# LightBoard.net
KiCad netlist of a schematic drawn in EAGLE
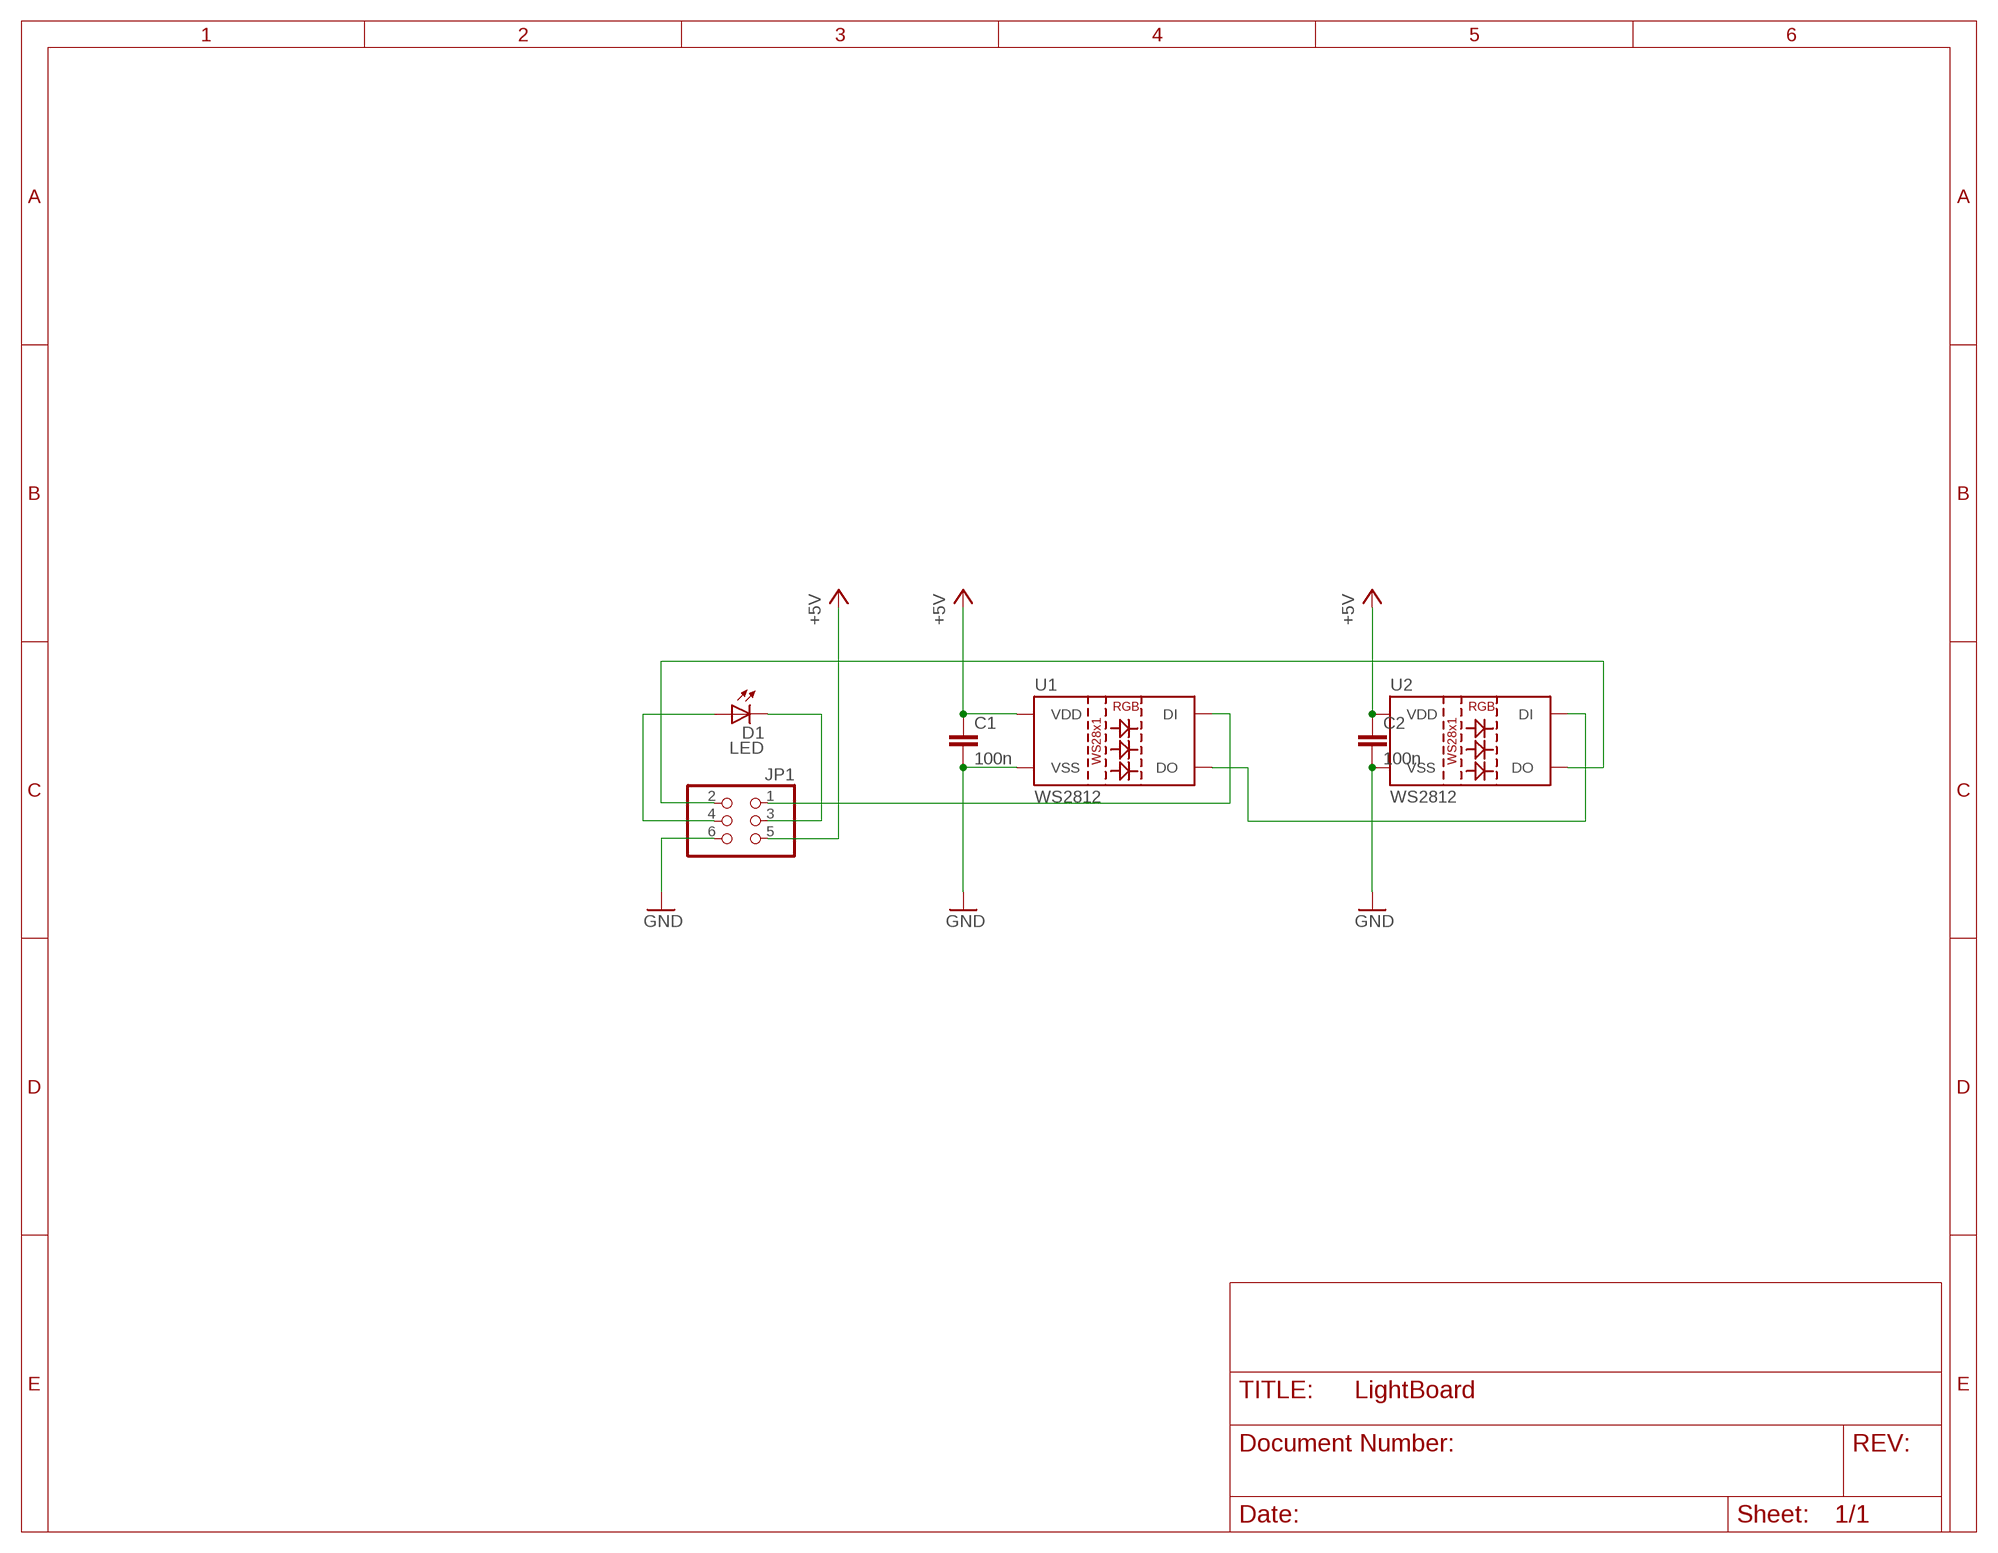
[diagram p0: schematic, sheet 1]

(export (version "E")
  (design (tool "Eeschema 10.0.6"))
  (components
    (comp (ref "C1")
      (value "100n")
      (footprint "eagle-import:C0603")
      (libsource (lib "eagle-import") (part "C-EUC0603"))
    )
    (comp (ref "C2")
      (value "100n")
      (footprint "eagle-import:C0603")
      (libsource (lib "eagle-import") (part "C-EUC0603"))
    )
    (comp (ref "D1")
      (value "LED")
      (footprint "eagle-import:LM561C")
      (libsource (lib "eagle-import") (part "LED"))
    )
    (comp (ref "JP1")
      (value "PINHD-2X3_2.54-SMD-90°")
      (footprint "eagle-import:2X03SMD_90")
      (libsource (lib "eagle-import") (part "PINHD-2X3_2.54-SMD-90°"))
    )
    (comp (ref "U1")
      (value "WS2812")
      (footprint "eagle-import:LED-TRICOLOR-5050-IC")
      (libsource (lib "eagle-import") (part "WS2812{dblquote}"))
    )
    (comp (ref "U2")
      (value "WS2812")
      (footprint "eagle-import:LED-TRICOLOR-5050-IC")
      (libsource (lib "eagle-import") (part "WS2812{dblquote}"))
    )
  )
  (nets
    (net (code "1") (name "+5V") (class "Default")
      (node (ref "C1") (pin "1") (pinfunction "1_1") (pintype "passive"))
      (node (ref "C2") (pin "1") (pinfunction "1_1") (pintype "passive"))
      (node (ref "JP1") (pin "5") (pinfunction "5_5") (pintype "passive"))
      (node (ref "U1") (pin "3") (pinfunction "VDD_3") (pintype "bidirectional"))
      (node (ref "U1") (pin "5") (pinfunction "VDD_5") (pintype "bidirectional"))
      (node (ref "U2") (pin "3") (pinfunction "VDD_3") (pintype "bidirectional"))
      (node (ref "U2") (pin "5") (pinfunction "VDD_5") (pintype "bidirectional"))
    )
    (net (code "2") (name "GND") (class "Default")
      (node (ref "C1") (pin "2") (pinfunction "2_2") (pintype "passive"))
      (node (ref "C2") (pin "2") (pinfunction "2_2") (pintype "passive"))
      (node (ref "JP1") (pin "6") (pinfunction "6_6") (pintype "passive"))
      (node (ref "U1") (pin "6") (pinfunction "VSS_6") (pintype "bidirectional"))
      (node (ref "U2") (pin "6") (pinfunction "VSS_6") (pintype "bidirectional"))
    )
    (net (code "3") (name "Net-(D1-A-PadA1)") (class "Default")
      (node (ref "D1") (pin "A1") (pinfunction "A_A1") (pintype "passive"))
      (node (ref "D1") (pin "A2") (pinfunction "A_A2") (pintype "passive"))
      (node (ref "D1") (pin "A3") (pinfunction "A_A3") (pintype "passive"))
      (node (ref "JP1") (pin "4") (pinfunction "4_4") (pintype "passive"))
    )
    (net (code "4") (name "Net-(D1-C-PadC1)") (class "Default")
      (node (ref "D1") (pin "C1") (pinfunction "C_C1") (pintype "passive"))
      (node (ref "D1") (pin "C2") (pinfunction "C_C2") (pintype "passive"))
      (node (ref "D1") (pin "C3") (pinfunction "C_C3") (pintype "passive"))
      (node (ref "JP1") (pin "3") (pinfunction "3_3") (pintype "passive"))
    )
    (net (code "5") (name "Net-(U1-DI)") (class "Default")
      (node (ref "JP1") (pin "1") (pinfunction "1_1") (pintype "passive"))
      (node (ref "U1") (pin "2") (pinfunction "DI_2") (pintype "bidirectional"))
    )
    (net (code "6") (name "Net-(U1-DO)") (class "Default")
      (node (ref "U1") (pin "1") (pinfunction "DO_1") (pintype "bidirectional"))
      (node (ref "U2") (pin "2") (pinfunction "DI_2") (pintype "bidirectional"))
    )
    (net (code "7") (name "Net-(U2-DO)") (class "Default")
      (node (ref "JP1") (pin "2") (pinfunction "2_2") (pintype "passive"))
      (node (ref "U2") (pin "1") (pinfunction "DO_1") (pintype "bidirectional"))
    )
  )
)
